# p1ac-001.net
KiCad netlist of a schematic drawn in EAGLE
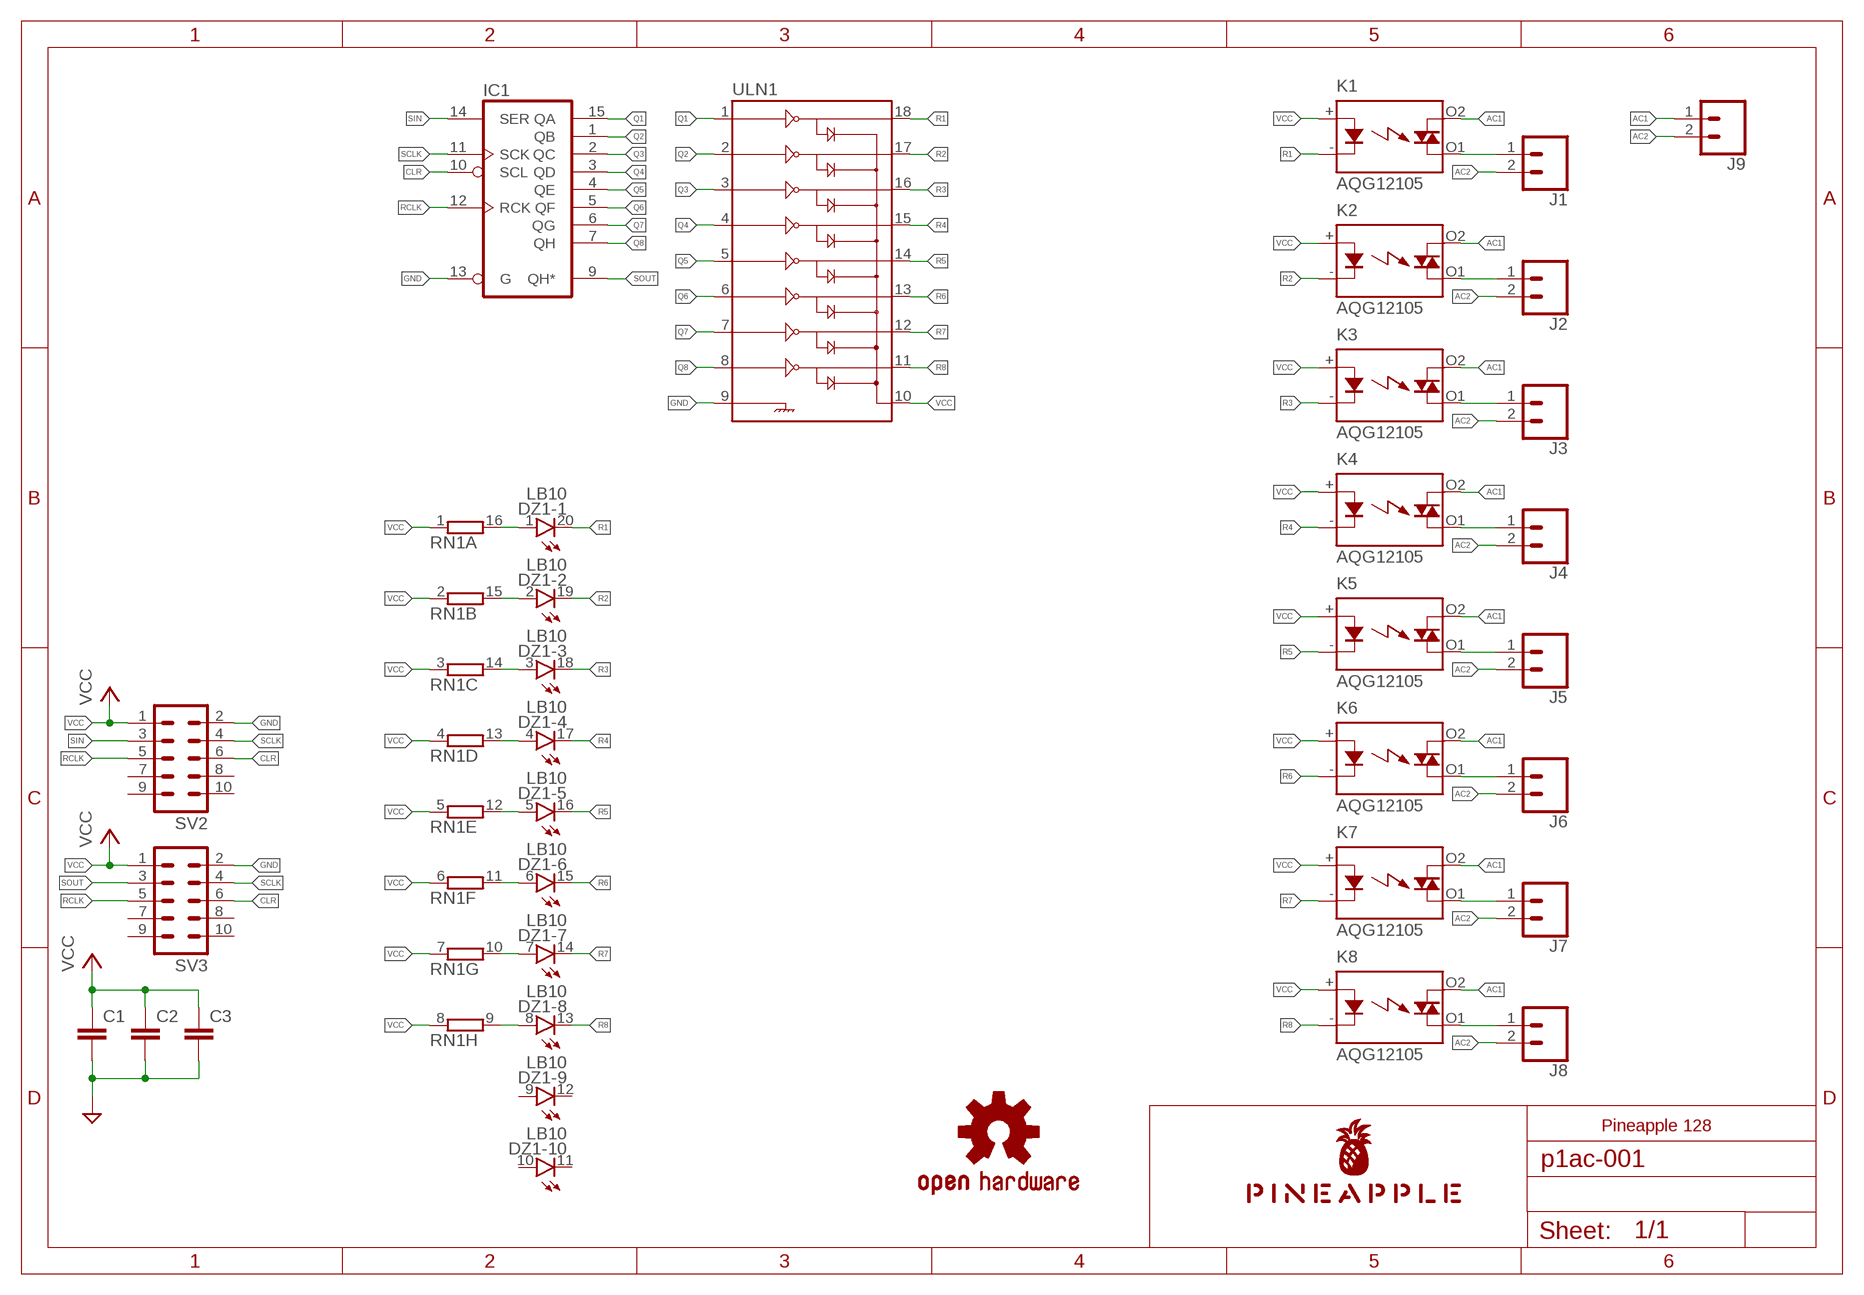
[diagram p0: schematic, sheet 1]

(export (version "E")
  (design (tool "Eeschema 10.0.6"))
  (components
    (comp (ref "C1")
      (value "C-EU025-024X044")
      (footprint "eagle-import:C025-024X044")
      (libsource (lib "eagle-import") (part "C-EU025-024X044"))
    )
    (comp (ref "C2")
      (value "C-EU025-024X044")
      (footprint "eagle-import:C025-024X044")
      (libsource (lib "eagle-import") (part "C-EU025-024X044"))
    )
    (comp (ref "C3")
      (value "C-EU025-024X044")
      (footprint "eagle-import:C025-024X044")
      (libsource (lib "eagle-import") (part "C-EU025-024X044"))
    )
    (comp (ref "DZ1")
      (value "LB10")
      (footprint "eagle-import:LB10")
      (libsource (lib "eagle-import") (part "LB10"))
    )
    (comp (ref "IC1")
      (value "74LS595N")
      (footprint "eagle-import:DIL16")
      (libsource (lib "eagle-import") (part "74595NLS"))
    )
    (comp (ref "J1")
      (value "CONN_02POLAR")
      (footprint "eagle-import:MOLEX-1X2")
      (libsource (lib "eagle-import") (part "CONN_02POLAR"))
    )
    (comp (ref "J2")
      (value "CONN_02POLAR")
      (footprint "eagle-import:MOLEX-1X2")
      (libsource (lib "eagle-import") (part "CONN_02POLAR"))
    )
    (comp (ref "J3")
      (value "CONN_02POLAR")
      (footprint "eagle-import:MOLEX-1X2")
      (libsource (lib "eagle-import") (part "CONN_02POLAR"))
    )
    (comp (ref "J4")
      (value "CONN_02POLAR")
      (footprint "eagle-import:MOLEX-1X2")
      (libsource (lib "eagle-import") (part "CONN_02POLAR"))
    )
    (comp (ref "J5")
      (value "CONN_02POLAR")
      (footprint "eagle-import:MOLEX-1X2")
      (libsource (lib "eagle-import") (part "CONN_02POLAR"))
    )
    (comp (ref "J6")
      (value "CONN_02POLAR")
      (footprint "eagle-import:MOLEX-1X2")
      (libsource (lib "eagle-import") (part "CONN_02POLAR"))
    )
    (comp (ref "J7")
      (value "CONN_02POLAR")
      (footprint "eagle-import:MOLEX-1X2")
      (libsource (lib "eagle-import") (part "CONN_02POLAR"))
    )
    (comp (ref "J8")
      (value "CONN_02POLAR")
      (footprint "eagle-import:MOLEX-1X2")
      (libsource (lib "eagle-import") (part "CONN_02POLAR"))
    )
    (comp (ref "J9")
      (value "CONN_02POLAR")
      (footprint "eagle-import:MOLEX-1X2")
      (libsource (lib "eagle-import") (part "CONN_02POLAR"))
    )
    (comp (ref "K1")
      (value "AQG12105")
      (footprint "eagle-import:AQG")
      (fields (field (name "MF") "AROMAT/ MATSUSHITA"))
      (libsource (lib "eagle-import") (part "AQG12105"))
    )
    (comp (ref "K2")
      (value "AQG12105")
      (footprint "eagle-import:AQG")
      (fields (field (name "MF") "AROMAT/ MATSUSHITA"))
      (libsource (lib "eagle-import") (part "AQG12105"))
    )
    (comp (ref "K3")
      (value "AQG12105")
      (footprint "eagle-import:AQG")
      (fields (field (name "MF") "AROMAT/ MATSUSHITA"))
      (libsource (lib "eagle-import") (part "AQG12105"))
    )
    (comp (ref "K4")
      (value "AQG12105")
      (footprint "eagle-import:AQG")
      (fields (field (name "MF") "AROMAT/ MATSUSHITA"))
      (libsource (lib "eagle-import") (part "AQG12105"))
    )
    (comp (ref "K5")
      (value "AQG12105")
      (footprint "eagle-import:AQG")
      (fields (field (name "MF") "AROMAT/ MATSUSHITA"))
      (libsource (lib "eagle-import") (part "AQG12105"))
    )
    (comp (ref "K6")
      (value "AQG12105")
      (footprint "eagle-import:AQG")
      (fields (field (name "MF") "AROMAT/ MATSUSHITA"))
      (libsource (lib "eagle-import") (part "AQG12105"))
    )
    (comp (ref "K7")
      (value "AQG12105")
      (footprint "eagle-import:AQG")
      (fields (field (name "MF") "AROMAT/ MATSUSHITA"))
      (libsource (lib "eagle-import") (part "AQG12105"))
    )
    (comp (ref "K8")
      (value "AQG12105")
      (footprint "eagle-import:AQG")
      (fields (field (name "MF") "AROMAT/ MATSUSHITA"))
      (libsource (lib "eagle-import") (part "AQG12105"))
    )
    (comp (ref "LOGO1")
      (value "OSHW-LOGOS-COPPER")
      (footprint "eagle-import:OSHW-LOGO-S_COPPER")
      (libsource (lib "eagle-import") (part "OSHW-LOGOS-COPPER"))
    )
    (comp (ref "RN1")
      (value "8R-N")
      (footprint "eagle-import:DIL16")
      (libsource (lib "eagle-import") (part "8R-N"))
    )
    (comp (ref "SV2")
      (value "ML10L")
      (footprint "eagle-import:ML10L")
      (libsource (lib "eagle-import") (part "ML10L"))
    )
    (comp (ref "SV3")
      (value "ML10L")
      (footprint "eagle-import:ML10L")
      (libsource (lib "eagle-import") (part "ML10L"))
    )
    (comp (ref "U$1")
      (value "PINEAPPLE450_SILK")
      (footprint "eagle-import:PINEAPPLE450_SILK")
      (libsource (lib "eagle-import") (part "PINEAPPLE450_SILK"))
    )
    (comp (ref "ULN1")
      (value "ULN2803DIP")
      (footprint "eagle-import:DIL18")
      (libsource (lib "eagle-import") (part "ULN2803DIP"))
    )
  )
  (nets
    (net (code "1") (name "AC1") (class "Default")
      (node (ref "J9") (pin "1") (pinfunction "1_1") (pintype "passive"))
      (node (ref "K1") (pin "O2") (pinfunction "DS1_O2") (pintype "passive"))
      (node (ref "K2") (pin "O2") (pinfunction "DS1_O2") (pintype "passive"))
      (node (ref "K3") (pin "O2") (pinfunction "DS1_O2") (pintype "passive"))
      (node (ref "K4") (pin "O2") (pinfunction "DS1_O2") (pintype "passive"))
      (node (ref "K5") (pin "O2") (pinfunction "DS1_O2") (pintype "passive"))
      (node (ref "K6") (pin "O2") (pinfunction "DS1_O2") (pintype "passive"))
      (node (ref "K7") (pin "O2") (pinfunction "DS1_O2") (pintype "passive"))
      (node (ref "K8") (pin "O2") (pinfunction "DS1_O2") (pintype "passive"))
    )
    (net (code "2") (name "AC2") (class "Default")
      (node (ref "J1") (pin "2") (pinfunction "2_2") (pintype "passive"))
      (node (ref "J2") (pin "2") (pinfunction "2_2") (pintype "passive"))
      (node (ref "J3") (pin "2") (pinfunction "2_2") (pintype "passive"))
      (node (ref "J4") (pin "2") (pinfunction "2_2") (pintype "passive"))
      (node (ref "J5") (pin "2") (pinfunction "2_2") (pintype "passive"))
      (node (ref "J6") (pin "2") (pinfunction "2_2") (pintype "passive"))
      (node (ref "J7") (pin "2") (pinfunction "2_2") (pintype "passive"))
      (node (ref "J8") (pin "2") (pinfunction "2_2") (pintype "passive"))
      (node (ref "J9") (pin "2") (pinfunction "2_2") (pintype "passive"))
    )
    (net (code "3") (name "CLR") (class "Default")
      (node (ref "IC1") (pin "10") (pinfunction "SCL_10") (pintype "input"))
      (node (ref "SV2") (pin "6") (pinfunction "6_6") (pintype "passive"))
      (node (ref "SV3") (pin "6") (pinfunction "6_6") (pintype "passive"))
    )
    (net (code "4") (name "GND") (class "Default")
      (node (ref "C1") (pin "2") (pinfunction "2_2") (pintype "passive"))
      (node (ref "C2") (pin "2") (pinfunction "2_2") (pintype "passive"))
      (node (ref "C3") (pin "2") (pinfunction "2_2") (pintype "passive"))
      (node (ref "IC1") (pin "13") (pinfunction "G_13") (pintype "input"))
      (node (ref "SV2") (pin "2") (pinfunction "2_2") (pintype "passive"))
      (node (ref "SV3") (pin "2") (pinfunction "2_2") (pintype "passive"))
      (node (ref "ULN1") (pin "9") (pinfunction "9_9") (pintype "bidirectional"))
    )
    (net (code "5") (name "Net-(DZ1A-A)") (class "Default")
      (node (ref "DZ1") (pin "1") (pinfunction "A_1") (pintype "passive"))
      (node (ref "RN1") (pin "16") (pinfunction "2_16") (pintype "passive"))
    )
    (net (code "6") (name "Net-(DZ1C-A)") (class "Default")
      (node (ref "DZ1") (pin "2") (pinfunction "A_2") (pintype "passive"))
      (node (ref "RN1") (pin "15") (pinfunction "2_15") (pintype "passive"))
    )
    (net (code "7") (name "Net-(DZ1D-A)") (class "Default")
      (node (ref "DZ1") (pin "3") (pinfunction "A_3") (pintype "passive"))
      (node (ref "RN1") (pin "14") (pinfunction "2_14") (pintype "passive"))
    )
    (net (code "8") (name "Net-(DZ1E-A)") (class "Default")
      (node (ref "DZ1") (pin "4") (pinfunction "A_4") (pintype "passive"))
      (node (ref "RN1") (pin "13") (pinfunction "2_13") (pintype "passive"))
    )
    (net (code "9") (name "Net-(DZ1F-A)") (class "Default")
      (node (ref "DZ1") (pin "5") (pinfunction "A_5") (pintype "passive"))
      (node (ref "RN1") (pin "12") (pinfunction "2_12") (pintype "passive"))
    )
    (net (code "10") (name "Net-(DZ1G-A)") (class "Default")
      (node (ref "DZ1") (pin "6") (pinfunction "A_6") (pintype "passive"))
      (node (ref "RN1") (pin "11") (pinfunction "2_11") (pintype "passive"))
    )
    (net (code "11") (name "Net-(DZ1H-A)") (class "Default")
      (node (ref "DZ1") (pin "7") (pinfunction "A_7") (pintype "passive"))
      (node (ref "RN1") (pin "10") (pinfunction "2_10") (pintype "passive"))
    )
    (net (code "12") (name "Net-(DZ1I-A)") (class "Default")
      (node (ref "DZ1") (pin "8") (pinfunction "A_8") (pintype "passive"))
      (node (ref "RN1") (pin "9") (pinfunction "2_9") (pintype "passive"))
    )
    (net (code "13") (name "Net-(K1-DS2)") (class "Default")
      (node (ref "J1") (pin "1") (pinfunction "1_1") (pintype "passive"))
      (node (ref "K1") (pin "O1") (pinfunction "DS2_O1") (pintype "passive"))
    )
    (net (code "14") (name "Net-(K2-DS2)") (class "Default")
      (node (ref "J2") (pin "1") (pinfunction "1_1") (pintype "passive"))
      (node (ref "K2") (pin "O1") (pinfunction "DS2_O1") (pintype "passive"))
    )
    (net (code "15") (name "Net-(K3-DS2)") (class "Default")
      (node (ref "J3") (pin "1") (pinfunction "1_1") (pintype "passive"))
      (node (ref "K3") (pin "O1") (pinfunction "DS2_O1") (pintype "passive"))
    )
    (net (code "16") (name "Net-(K4-DS2)") (class "Default")
      (node (ref "J4") (pin "1") (pinfunction "1_1") (pintype "passive"))
      (node (ref "K4") (pin "O1") (pinfunction "DS2_O1") (pintype "passive"))
    )
    (net (code "17") (name "Net-(K5-DS2)") (class "Default")
      (node (ref "J5") (pin "1") (pinfunction "1_1") (pintype "passive"))
      (node (ref "K5") (pin "O1") (pinfunction "DS2_O1") (pintype "passive"))
    )
    (net (code "18") (name "Net-(K6-DS2)") (class "Default")
      (node (ref "J6") (pin "1") (pinfunction "1_1") (pintype "passive"))
      (node (ref "K6") (pin "O1") (pinfunction "DS2_O1") (pintype "passive"))
    )
    (net (code "19") (name "Net-(K7-DS2)") (class "Default")
      (node (ref "J7") (pin "1") (pinfunction "1_1") (pintype "passive"))
      (node (ref "K7") (pin "O1") (pinfunction "DS2_O1") (pintype "passive"))
    )
    (net (code "20") (name "Net-(K8-DS2)") (class "Default")
      (node (ref "J8") (pin "1") (pinfunction "1_1") (pintype "passive"))
      (node (ref "K8") (pin "O1") (pinfunction "DS2_O1") (pintype "passive"))
    )
    (net (code "21") (name "Q1") (class "Default")
      (node (ref "IC1") (pin "15") (pinfunction "QA_15") (pintype "tri_state"))
      (node (ref "ULN1") (pin "1") (pinfunction "1_1") (pintype "bidirectional"))
    )
    (net (code "22") (name "Q2") (class "Default")
      (node (ref "IC1") (pin "1") (pinfunction "QB_1") (pintype "tri_state"))
      (node (ref "ULN1") (pin "2") (pinfunction "2_2") (pintype "bidirectional"))
    )
    (net (code "23") (name "Q3") (class "Default")
      (node (ref "IC1") (pin "2") (pinfunction "QC_2") (pintype "tri_state"))
      (node (ref "ULN1") (pin "3") (pinfunction "3_3") (pintype "bidirectional"))
    )
    (net (code "24") (name "Q4") (class "Default")
      (node (ref "IC1") (pin "3") (pinfunction "QD_3") (pintype "tri_state"))
      (node (ref "ULN1") (pin "4") (pinfunction "4_4") (pintype "bidirectional"))
    )
    (net (code "25") (name "Q5") (class "Default")
      (node (ref "IC1") (pin "4") (pinfunction "QE_4") (pintype "tri_state"))
      (node (ref "ULN1") (pin "5") (pinfunction "5_5") (pintype "bidirectional"))
    )
    (net (code "26") (name "Q6") (class "Default")
      (node (ref "IC1") (pin "5") (pinfunction "QF_5") (pintype "tri_state"))
      (node (ref "ULN1") (pin "6") (pinfunction "6_6") (pintype "bidirectional"))
    )
    (net (code "27") (name "Q7") (class "Default")
      (node (ref "IC1") (pin "6") (pinfunction "QG_6") (pintype "tri_state"))
      (node (ref "ULN1") (pin "7") (pinfunction "7_7") (pintype "bidirectional"))
    )
    (net (code "28") (name "Q8") (class "Default")
      (node (ref "IC1") (pin "7") (pinfunction "QH_7") (pintype "tri_state"))
      (node (ref "ULN1") (pin "8") (pinfunction "8_8") (pintype "bidirectional"))
    )
    (net (code "29") (name "R1") (class "Default")
      (node (ref "DZ1") (pin "20") (pinfunction "C_20") (pintype "passive"))
      (node (ref "K1") (pin "-") (pinfunction "K_-") (pintype "passive"))
      (node (ref "ULN1") (pin "18") (pinfunction "18_18") (pintype "bidirectional"))
    )
    (net (code "30") (name "R2") (class "Default")
      (node (ref "DZ1") (pin "19") (pinfunction "C_19") (pintype "passive"))
      (node (ref "K2") (pin "-") (pinfunction "K_-") (pintype "passive"))
      (node (ref "ULN1") (pin "17") (pinfunction "17_17") (pintype "bidirectional"))
    )
    (net (code "31") (name "R3") (class "Default")
      (node (ref "DZ1") (pin "18") (pinfunction "C_18") (pintype "passive"))
      (node (ref "K3") (pin "-") (pinfunction "K_-") (pintype "passive"))
      (node (ref "ULN1") (pin "16") (pinfunction "16_16") (pintype "bidirectional"))
    )
    (net (code "32") (name "R4") (class "Default")
      (node (ref "DZ1") (pin "17") (pinfunction "C_17") (pintype "passive"))
      (node (ref "K4") (pin "-") (pinfunction "K_-") (pintype "passive"))
      (node (ref "ULN1") (pin "15") (pinfunction "15_15") (pintype "bidirectional"))
    )
    (net (code "33") (name "R5") (class "Default")
      (node (ref "DZ1") (pin "16") (pinfunction "C_16") (pintype "passive"))
      (node (ref "K5") (pin "-") (pinfunction "K_-") (pintype "passive"))
      (node (ref "ULN1") (pin "14") (pinfunction "14_14") (pintype "bidirectional"))
    )
    (net (code "34") (name "R6") (class "Default")
      (node (ref "DZ1") (pin "15") (pinfunction "C_15") (pintype "passive"))
      (node (ref "K6") (pin "-") (pinfunction "K_-") (pintype "passive"))
      (node (ref "ULN1") (pin "13") (pinfunction "13_13") (pintype "bidirectional"))
    )
    (net (code "35") (name "R7") (class "Default")
      (node (ref "DZ1") (pin "14") (pinfunction "C_14") (pintype "passive"))
      (node (ref "K7") (pin "-") (pinfunction "K_-") (pintype "passive"))
      (node (ref "ULN1") (pin "12") (pinfunction "12_12") (pintype "bidirectional"))
    )
    (net (code "36") (name "R8") (class "Default")
      (node (ref "DZ1") (pin "13") (pinfunction "C_13") (pintype "passive"))
      (node (ref "K8") (pin "-") (pinfunction "K_-") (pintype "passive"))
      (node (ref "ULN1") (pin "11") (pinfunction "11_11") (pintype "bidirectional"))
    )
    (net (code "37") (name "RCLK") (class "Default")
      (node (ref "IC1") (pin "12") (pinfunction "RCK_12") (pintype "input"))
      (node (ref "SV2") (pin "5") (pinfunction "5_5") (pintype "passive"))
      (node (ref "SV3") (pin "5") (pinfunction "5_5") (pintype "passive"))
    )
    (net (code "38") (name "SCLK") (class "Default")
      (node (ref "IC1") (pin "11") (pinfunction "SCK_11") (pintype "input"))
      (node (ref "SV2") (pin "4") (pinfunction "4_4") (pintype "passive"))
      (node (ref "SV3") (pin "4") (pinfunction "4_4") (pintype "passive"))
    )
    (net (code "39") (name "SIN") (class "Default")
      (node (ref "IC1") (pin "14") (pinfunction "SER_14") (pintype "input"))
      (node (ref "SV2") (pin "3") (pinfunction "3_3") (pintype "passive"))
    )
    (net (code "40") (name "SOUT") (class "Default")
      (node (ref "IC1") (pin "9") (pinfunction "QH*_9") (pintype "tri_state"))
      (node (ref "SV3") (pin "3") (pinfunction "3_3") (pintype "passive"))
    )
    (net (code "41") (name "VCC") (class "Default")
      (node (ref "C1") (pin "1") (pinfunction "1_1") (pintype "passive"))
      (node (ref "C2") (pin "1") (pinfunction "1_1") (pintype "passive"))
      (node (ref "C3") (pin "1") (pinfunction "1_1") (pintype "passive"))
      (node (ref "K1") (pin "+") (pinfunction "A_+") (pintype "passive"))
      (node (ref "K2") (pin "+") (pinfunction "A_+") (pintype "passive"))
      (node (ref "K3") (pin "+") (pinfunction "A_+") (pintype "passive"))
      (node (ref "K4") (pin "+") (pinfunction "A_+") (pintype "passive"))
      (node (ref "K5") (pin "+") (pinfunction "A_+") (pintype "passive"))
      (node (ref "K6") (pin "+") (pinfunction "A_+") (pintype "passive"))
      (node (ref "K7") (pin "+") (pinfunction "A_+") (pintype "passive"))
      (node (ref "K8") (pin "+") (pinfunction "A_+") (pintype "passive"))
      (node (ref "RN1") (pin "1") (pinfunction "1_1") (pintype "passive"))
      (node (ref "RN1") (pin "2") (pinfunction "1_2") (pintype "passive"))
      (node (ref "RN1") (pin "3") (pinfunction "1_3") (pintype "passive"))
      (node (ref "RN1") (pin "4") (pinfunction "1_4") (pintype "passive"))
      (node (ref "RN1") (pin "5") (pinfunction "1_5") (pintype "passive"))
      (node (ref "RN1") (pin "6") (pinfunction "1_6") (pintype "passive"))
      (node (ref "RN1") (pin "7") (pinfunction "1_7") (pintype "passive"))
      (node (ref "RN1") (pin "8") (pinfunction "1_8") (pintype "passive"))
      (node (ref "SV2") (pin "1") (pinfunction "1_1") (pintype "passive"))
      (node (ref "SV3") (pin "1") (pinfunction "1_1") (pintype "passive"))
      (node (ref "ULN1") (pin "10") (pinfunction "10_10") (pintype "bidirectional"))
    )
    (net (code "42") (name "unconnected-(DZ1B-A-Pad10)") (class "Default")
      (node (ref "DZ1") (pin "10") (pinfunction "A_10") (pintype "passive"))
    )
    (net (code "43") (name "unconnected-(DZ1B-C-Pad11)") (class "Default")
      (node (ref "DZ1") (pin "11") (pinfunction "C_11") (pintype "passive"))
    )
    (net (code "44") (name "unconnected-(DZ1J-A-Pad9)") (class "Default")
      (node (ref "DZ1") (pin "9") (pinfunction "A_9") (pintype "passive"))
    )
    (net (code "45") (name "unconnected-(DZ1J-C-Pad12)") (class "Default")
      (node (ref "DZ1") (pin "12") (pinfunction "C_12") (pintype "passive"))
    )
    (net (code "46") (name "unconnected-(SV2-Pad7)") (class "Default")
      (node (ref "SV2") (pin "7") (pinfunction "7_7") (pintype "passive"))
    )
    (net (code "47") (name "unconnected-(SV2-Pad8)") (class "Default")
      (node (ref "SV2") (pin "8") (pinfunction "8_8") (pintype "passive"))
    )
    (net (code "48") (name "unconnected-(SV2-Pad9)") (class "Default")
      (node (ref "SV2") (pin "9") (pinfunction "9_9") (pintype "passive"))
    )
    (net (code "49") (name "unconnected-(SV2-Pad10)") (class "Default")
      (node (ref "SV2") (pin "10") (pinfunction "10_10") (pintype "passive"))
    )
    (net (code "50") (name "unconnected-(SV3-Pad7)") (class "Default")
      (node (ref "SV3") (pin "7") (pinfunction "7_7") (pintype "passive"))
    )
    (net (code "51") (name "unconnected-(SV3-Pad8)") (class "Default")
      (node (ref "SV3") (pin "8") (pinfunction "8_8") (pintype "passive"))
    )
    (net (code "52") (name "unconnected-(SV3-Pad9)") (class "Default")
      (node (ref "SV3") (pin "9") (pinfunction "9_9") (pintype "passive"))
    )
    (net (code "53") (name "unconnected-(SV3-Pad10)") (class "Default")
      (node (ref "SV3") (pin "10") (pinfunction "10_10") (pintype "passive"))
    )
  )
)
